# HM-10.net
KiCad netlist of a schematic drawn in Altium Designer
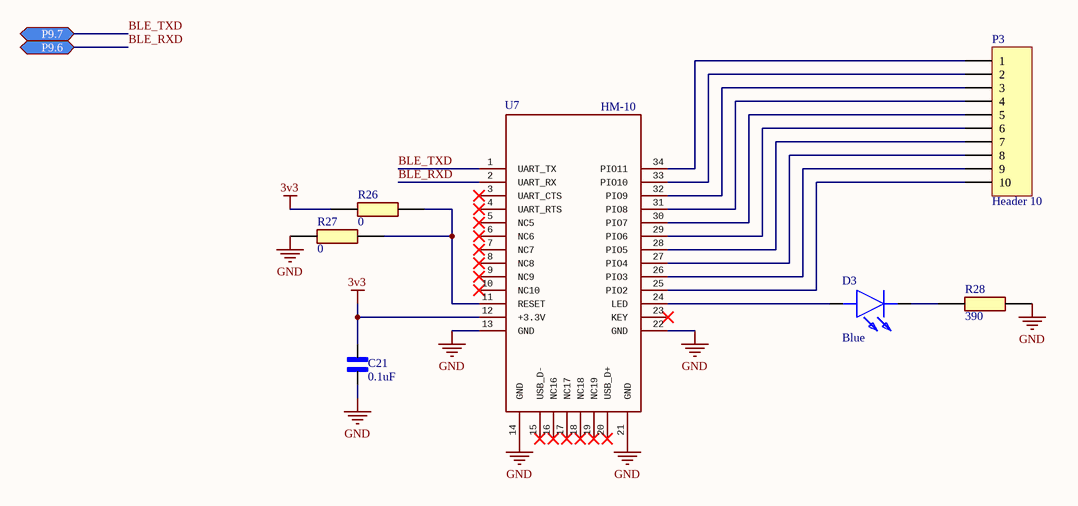
[diagram p0: HM-10.schDoc]

(export (version "E")
  (design (tool "Eeschema 10.0.6"))
  (components
    (comp (ref "C21")
      (value "0.1uF")
      (footprint "CAPC1005X55N")
      (description "Capacitor X7R 0402 (1005 Metric)")
      (fields (field (name "MANUFACTURER") "AVX") (field (name "TOLERANCE") "5%"))
      (libsource (lib "UngBung") (part "Multilayer Ceramic Cap. 0402 (1005 Metric)"))
    )
    (comp (ref "D3")
      (value "APHHS1005LQBC/D-V")
      (footprint "APHHS1005LQBC/D-V")
      (description "BLUE - Standard LEDs - SMD 1.0X0.5MM")
      (fields (field (name "MANUFACTURER") "Kingbright") (field (name "COLOR") "Blue"))
      (libsource (lib "UngBung") (part "APHHS1005LQBC/D-V"))
    )
    (comp (ref "P3")
      (value "Header 10")
      (footprint "HDR1X10")
      (description "Header, 10-Pin")
      (fields (field (name "PUBLISHER") "Altium Limited"))
      (libsource (lib "Miscellaneous Connectors") (part "Header 10"))
    )
    (comp (ref "R26")
      (value "0")
      (footprint "Resistor 0603")
      (fields
        (field (name "MANUFACTURER") "Vishay / Dale")
        (field (name "TOLERANCE") "*tolerance*")
        (field (name "Comment") "Resistor 0603")
      )
      (libsource (lib "UngBung") (part "Resistor 0603"))
    )
    (comp (ref "R27")
      (value "0")
      (footprint "Resistor 0603")
      (fields
        (field (name "MANUFACTURER") "Vishay / Dale")
        (field (name "TOLERANCE") "*tolerance*")
        (field (name "Comment") "Resistor 0603")
      )
      (libsource (lib "UngBung") (part "Resistor 0603"))
    )
    (comp (ref "R28")
      (value "390")
      (footprint "Thin-Film Resistor 0402 (1005 Metric)")
      (description "Resistor, 0402 Package size")
      (fields (field (name "MANUFACTURER") "Yageo") (field (name "TOLERANCE") "1%"))
      (libsource (lib "UngBung") (part "Resistor 0402 (1005 Metric)"))
    )
    (comp (ref "U7")
      (value "HM-10")
      (footprint "HM-10")
      (description "BLE Communication module, send/receive communications via UART")
      (fields (field (name "MANUFACTURER") "DSD Tech"))
      (libsource (lib "UngBung") (part "HM-10"))
    )
  )
  (nets
    (net (code "1") (name "/BLE_RXD") (class "Default")
      (node (ref "U7") (pin "2") (pinfunction "UART_RX_2") (pintype "passive"))
    )
    (net (code "2") (name "/BLE_TXD") (class "Default")
      (node (ref "U7") (pin "1") (pinfunction "UART_TX_1") (pintype "passive"))
    )
    (net (code "3") (name "3v3") (class "Default")
      (node (ref "C21") (pin "2") (pinfunction "2_2") (pintype "passive"))
      (node (ref "R26") (pin "1") (pinfunction "1_1") (pintype "passive"))
      (node (ref "U7") (pin "12") (pinfunction "+3.3V_12") (pintype "passive"))
    )
    (net (code "4") (name "GND") (class "Default")
      (node (ref "C21") (pin "1") (pinfunction "1_1") (pintype "passive"))
      (node (ref "R27") (pin "1") (pinfunction "1_1") (pintype "passive"))
      (node (ref "R28") (pin "2") (pinfunction "2_2") (pintype "passive"))
      (node (ref "U7") (pin "13") (pinfunction "GND_13") (pintype "passive"))
      (node (ref "U7") (pin "14") (pinfunction "GND_14") (pintype "passive"))
      (node (ref "U7") (pin "21") (pinfunction "GND_21") (pintype "passive"))
      (node (ref "U7") (pin "22") (pinfunction "GND_22") (pintype "passive"))
    )
    (net (code "5") (name "Net-(D3-A)") (class "Default")
      (node (ref "D3") (pin "2") (pinfunction "A_2") (pintype "passive"))
      (node (ref "U7") (pin "24") (pinfunction "LED_24") (pintype "passive"))
    )
    (net (code "6") (name "Net-(D3-K)") (class "Default")
      (node (ref "D3") (pin "1") (pinfunction "K_1") (pintype "passive"))
      (node (ref "R28") (pin "1") (pinfunction "1_1") (pintype "passive"))
    )
    (net (code "7") (name "Net-(U7-PIO2)") (class "Default")
      (node (ref "P3") (pin "10") (pinfunction "10_10") (pintype "passive"))
      (node (ref "U7") (pin "25") (pinfunction "PIO2_25") (pintype "passive"))
    )
    (net (code "8") (name "Net-(U7-PIO3)") (class "Default")
      (node (ref "P3") (pin "9") (pinfunction "9_9") (pintype "passive"))
      (node (ref "U7") (pin "26") (pinfunction "PIO3_26") (pintype "passive"))
    )
    (net (code "9") (name "Net-(U7-PIO4)") (class "Default")
      (node (ref "P3") (pin "8") (pinfunction "8_8") (pintype "passive"))
      (node (ref "U7") (pin "27") (pinfunction "PIO4_27") (pintype "passive"))
    )
    (net (code "10") (name "Net-(U7-PIO5)") (class "Default")
      (node (ref "P3") (pin "7") (pinfunction "7_7") (pintype "passive"))
      (node (ref "U7") (pin "28") (pinfunction "PIO5_28") (pintype "passive"))
    )
    (net (code "11") (name "Net-(U7-PIO6)") (class "Default")
      (node (ref "P3") (pin "6") (pinfunction "6_6") (pintype "passive"))
      (node (ref "U7") (pin "29") (pinfunction "PIO6_29") (pintype "passive"))
    )
    (net (code "12") (name "Net-(U7-PIO7)") (class "Default")
      (node (ref "P3") (pin "5") (pinfunction "5_5") (pintype "passive"))
      (node (ref "U7") (pin "30") (pinfunction "PIO7_30") (pintype "passive"))
    )
    (net (code "13") (name "Net-(U7-PIO8)") (class "Default")
      (node (ref "P3") (pin "4") (pinfunction "4_4") (pintype "passive"))
      (node (ref "U7") (pin "31") (pinfunction "PIO8_31") (pintype "passive"))
    )
    (net (code "14") (name "Net-(U7-PIO9)") (class "Default")
      (node (ref "P3") (pin "3") (pinfunction "3_3") (pintype "passive"))
      (node (ref "U7") (pin "32") (pinfunction "PIO9_32") (pintype "passive"))
    )
    (net (code "15") (name "Net-(U7-PIO10)") (class "Default")
      (node (ref "P3") (pin "2") (pinfunction "2_2") (pintype "passive"))
      (node (ref "U7") (pin "33") (pinfunction "PIO10_33") (pintype "passive"))
    )
    (net (code "16") (name "Net-(U7-PIO11)") (class "Default")
      (node (ref "P3") (pin "1") (pinfunction "1_1") (pintype "passive"))
      (node (ref "U7") (pin "34") (pinfunction "PIO11_34") (pintype "passive"))
    )
    (net (code "17") (name "Net-(U7-RESET)") (class "Default")
      (node (ref "R26") (pin "2") (pinfunction "2_2") (pintype "passive"))
      (node (ref "R27") (pin "2") (pinfunction "2_2") (pintype "passive"))
      (node (ref "U7") (pin "11") (pinfunction "RESET_11") (pintype "passive"))
    )
    (net (code "18") (name "unconnected-(U7-KEY-Pad23)") (class "Default")
      (node (ref "U7") (pin "23") (pinfunction "KEY_23") (pintype "passive+no_connect"))
    )
    (net (code "19") (name "unconnected-(U7-NC5-Pad5)") (class "Default")
      (node (ref "U7") (pin "5") (pinfunction "NC5_5") (pintype "passive+no_connect"))
    )
    (net (code "20") (name "unconnected-(U7-NC6-Pad6)") (class "Default")
      (node (ref "U7") (pin "6") (pinfunction "NC6_6") (pintype "passive+no_connect"))
    )
    (net (code "21") (name "unconnected-(U7-NC7-Pad7)") (class "Default")
      (node (ref "U7") (pin "7") (pinfunction "NC7_7") (pintype "passive+no_connect"))
    )
    (net (code "22") (name "unconnected-(U7-NC8-Pad8)") (class "Default")
      (node (ref "U7") (pin "8") (pinfunction "NC8_8") (pintype "passive+no_connect"))
    )
    (net (code "23") (name "unconnected-(U7-NC9-Pad9)") (class "Default")
      (node (ref "U7") (pin "9") (pinfunction "NC9_9") (pintype "passive+no_connect"))
    )
    (net (code "24") (name "unconnected-(U7-NC10-Pad10)") (class "Default")
      (node (ref "U7") (pin "10") (pinfunction "NC10_10") (pintype "passive+no_connect"))
    )
    (net (code "25") (name "unconnected-(U7-NC16-Pad16)") (class "Default")
      (node (ref "U7") (pin "16") (pinfunction "NC16_16") (pintype "passive+no_connect"))
    )
    (net (code "26") (name "unconnected-(U7-NC17-Pad17)") (class "Default")
      (node (ref "U7") (pin "17") (pinfunction "NC17_17") (pintype "passive+no_connect"))
    )
    (net (code "27") (name "unconnected-(U7-NC18-Pad18)") (class "Default")
      (node (ref "U7") (pin "18") (pinfunction "NC18_18") (pintype "passive+no_connect"))
    )
    (net (code "28") (name "unconnected-(U7-NC19-Pad19)") (class "Default")
      (node (ref "U7") (pin "19") (pinfunction "NC19_19") (pintype "passive+no_connect"))
    )
    (net (code "29") (name "unconnected-(U7-UART_CTS-Pad3)") (class "Default")
      (node (ref "U7") (pin "3") (pinfunction "UART_CTS_3") (pintype "passive+no_connect"))
    )
    (net (code "30") (name "unconnected-(U7-UART_RTS-Pad4)") (class "Default")
      (node (ref "U7") (pin "4") (pinfunction "UART_RTS_4") (pintype "passive+no_connect"))
    )
    (net (code "31") (name "unconnected-(U7-USB_D+-Pad20)") (class "Default")
      (node (ref "U7") (pin "20") (pinfunction "USB_D+_20") (pintype "passive+no_connect"))
    )
    (net (code "32") (name "unconnected-(U7-USB_D--Pad15)") (class "Default")
      (node (ref "U7") (pin "15") (pinfunction "USB_D-_15") (pintype "passive+no_connect"))
    )
  )
)
